# PCA_0005_FULL_CB_Servo_REV_B.net
KiCad netlist of a schematic drawn in Altium Designer
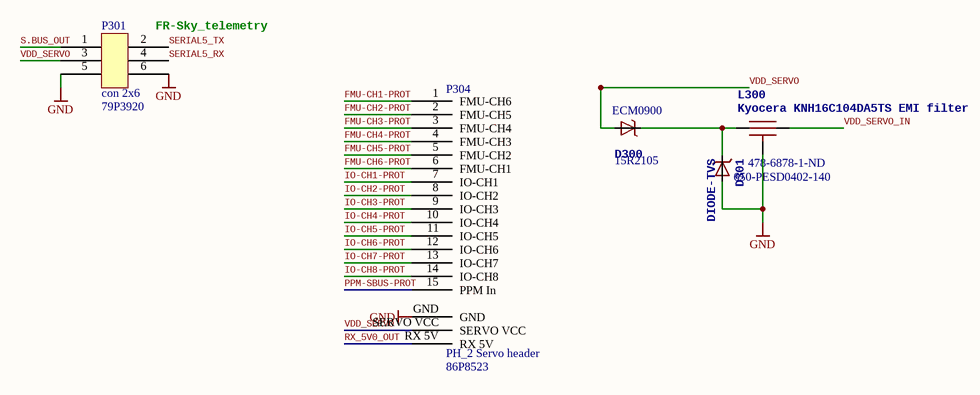
[diagram p0: PCA_0005_FULL_CB_Servo_REV_B.SchDoc]

(export (version "E")
  (design (tool "Eeschema 10.0.6"))
  (components
    (comp (ref "D300")
      (value "MSS1P4-M3")
      (footprint "MICROSMP")
      (description "Diode, Schottky, 40V, 1A, MicroSMP, SMD")
      (fields (field (name "SUPPLIER PART NUMBER 1") "15R2105") (field (name "3DR_PARTNO") "ECM0900"))
      (libsource (lib "PCA_0005_FULL_CB_REV_A") (part "DIODE-SCHOTTKY_MSMP"))
    )
    (comp (ref "D301")
      (value "DIODE-TVS")
      (footprint "0402-TVS")
      (description "Diode, TVS, 14VWM, 40VC, 0402, SMD")
      (fields
        (field (name "SUPPLIER PART NUMBER 1") "650-PESD0402-140")
        (field (name "3DR_PARTNO") "ECM0837")
      )
      (libsource (lib "PCA_0005_FULL_CB_REV_A") (part "DIODE-TVS"))
    )
    (comp (ref "L300")
      (value "Kyocera KNH16C104DA5TS EMI filter")
      (footprint "KYOCERA-KNH16-DA")
      (description "Capacitor, Filter, 0.1uF, 25V, 2A, 0603, SMD")
      (fields (field (name "SUPPLIER PART NUMBER 1") "478-6878-1-ND") (field (name "3DR_PARTNO") "ECM0719"))
      (libsource (lib "PCA_0005_FULL_CB_REV_A") (part "KNH16C104DA5TS"))
    )
    (comp (ref "P301")
      (value "con 2x6")
      (footprint "TSW-103-07-G-D")
      (description "Connector, Header, 6Pos, 2.54MM, Vert, THT, Au")
      (fields (field (name "SUPPLIER PART NUMBER 1") "79P3920") (field (name "3DR_PARTNO") "PRT0445"))
      (libsource (lib "PCA_0005_FULL_CB_REV_A") (part "con 2x6"))
    )
    (comp (ref "P304")
      (value "PH_2 Servo header")
      (footprint "TSW-115-08-G-T-RA")
      (description "Connector, Header, 45Pos, 2.54MM, R/A, THT, Tin")
      (fields (field (name "SUPPLIER PART NUMBER 1") "86P8523") (field (name "3DR_PARTNO") "PRT0446"))
      (libsource (lib "PCA_0005_FULL_CB_REV_A") (part "PH_2 Servo header"))
    )
  )
  (nets
    (net (code "1") (name "/FMU-CH1-PROT") (class "Default")
      (node (ref "P304") (pin "1") (pinfunction "FMU-CH6_1") (pintype "passive"))
    )
    (net (code "2") (name "/FMU-CH2-PROT") (class "Default")
      (node (ref "P304") (pin "2") (pinfunction "FMU-CH5_2") (pintype "passive"))
    )
    (net (code "3") (name "/FMU-CH3-PROT") (class "Default")
      (node (ref "P304") (pin "3") (pinfunction "FMU-CH4_3") (pintype "passive"))
    )
    (net (code "4") (name "/FMU-CH4-PROT") (class "Default")
      (node (ref "P304") (pin "4") (pinfunction "FMU-CH3_4") (pintype "passive"))
    )
    (net (code "5") (name "/FMU-CH5-PROT") (class "Default")
      (node (ref "P304") (pin "5") (pinfunction "FMU-CH2_5") (pintype "passive"))
    )
    (net (code "6") (name "/FMU-CH6-PROT") (class "Default")
      (node (ref "P304") (pin "6") (pinfunction "FMU-CH1_6") (pintype "passive"))
    )
    (net (code "7") (name "/IO-CH1-PROT") (class "Default")
      (node (ref "P304") (pin "7") (pinfunction "IO-CH1_7") (pintype "passive"))
    )
    (net (code "8") (name "/IO-CH2-PROT") (class "Default")
      (node (ref "P304") (pin "8") (pinfunction "IO-CH2_8") (pintype "passive"))
    )
    (net (code "9") (name "/IO-CH3-PROT") (class "Default")
      (node (ref "P304") (pin "9") (pinfunction "IO-CH3_9") (pintype "passive"))
    )
    (net (code "10") (name "/IO-CH4-PROT") (class "Default")
      (node (ref "P304") (pin "10") (pinfunction "IO-CH4_10") (pintype "passive"))
    )
    (net (code "11") (name "/IO-CH5-PROT") (class "Default")
      (node (ref "P304") (pin "11") (pinfunction "IO-CH5_11") (pintype "passive"))
    )
    (net (code "12") (name "/IO-CH6-PROT") (class "Default")
      (node (ref "P304") (pin "12") (pinfunction "IO-CH6_12") (pintype "passive"))
    )
    (net (code "13") (name "/IO-CH7-PROT") (class "Default")
      (node (ref "P304") (pin "13") (pinfunction "IO-CH7_13") (pintype "passive"))
    )
    (net (code "14") (name "/IO-CH8-PROT") (class "Default")
      (node (ref "P304") (pin "14") (pinfunction "IO-CH8_14") (pintype "passive"))
    )
    (net (code "15") (name "/PPM-SBUS-PROT") (class "Default")
      (node (ref "P304") (pin "15") (pinfunction "PPM_In_15") (pintype "passive"))
    )
    (net (code "16") (name "/RX_5V0_OUT") (class "Default")
      (node (ref "P304") (pin "RX_5V") (pinfunction "RX_5V_RX_5V") (pintype "passive"))
    )
    (net (code "17") (name "/S.BUS_OUT") (class "Default")
      (node (ref "P301") (pin "1") (pinfunction "1_1") (pintype "passive"))
    )
    (net (code "18") (name "/SERIAL5_RX") (class "Default")
      (node (ref "P301") (pin "4") (pinfunction "4_4") (pintype "passive"))
    )
    (net (code "19") (name "/SERIAL5_TX") (class "Default")
      (node (ref "P301") (pin "2") (pinfunction "2_2") (pintype "passive"))
    )
    (net (code "20") (name "/VDD_SERVO") (class "Default")
      (node (ref "D300") (pin "ANODE") (pinfunction "A_ANODE") (pintype "passive"))
      (node (ref "P301") (pin "3") (pinfunction "3_3") (pintype "passive"))
      (node (ref "P304") (pin "SERVO_VCC") (pinfunction "SERVO_VCC_SERVO_VCC") (pintype "passive"))
    )
    (net (code "21") (name "/VDD_SERVO_IN") (class "Default")
      (node (ref "L300") (pin "P$2") (pinfunction "P$2_P$2") (pintype "passive"))
    )
    (net (code "22") (name "GND") (class "Default")
      (node (ref "D301") (pin "A") (pinfunction "A_A") (pintype "passive"))
      (node (ref "L300") (pin "GND") (pinfunction "GND_GND") (pintype "passive"))
      (node (ref "P301") (pin "5") (pinfunction "5_5") (pintype "passive"))
      (node (ref "P301") (pin "6") (pinfunction "6_6") (pintype "passive"))
      (node (ref "P304") (pin "GND") (pinfunction "GND_GND") (pintype "passive"))
    )
    (net (code "23") (name "Net-(D300-C)") (class "Default")
      (node (ref "D300") (pin "CATHODE") (pinfunction "C_CATHODE") (pintype "passive"))
      (node (ref "D301") (pin "C") (pinfunction "C_C") (pintype "passive"))
      (node (ref "L300") (pin "P$1") (pinfunction "P$1_P$1") (pintype "passive"))
    )
  )
)
